# kinks_v41.net
KiCad netlist of a schematic drawn in EAGLE
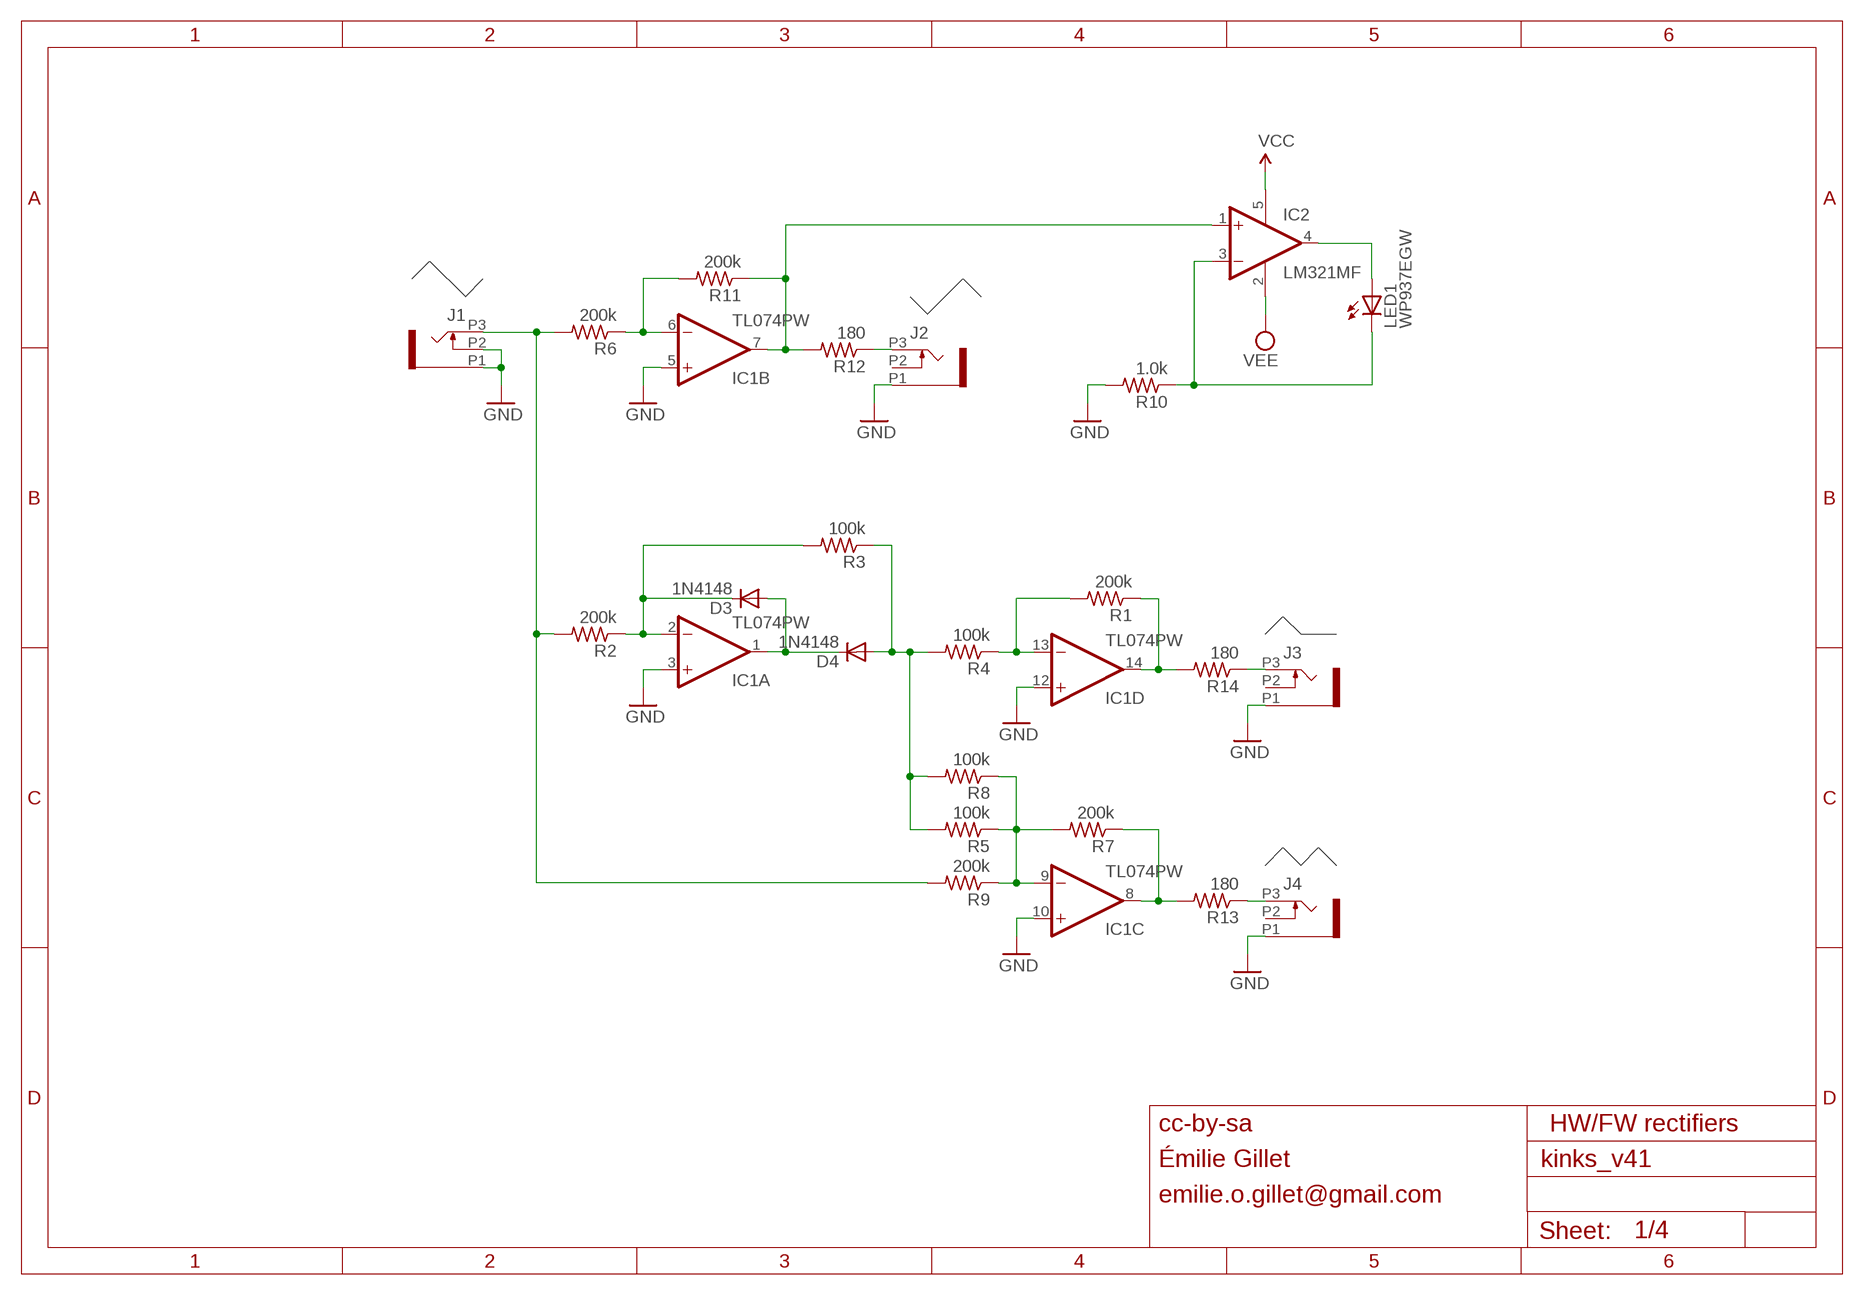
[diagram p0: schematic, sheet 1]
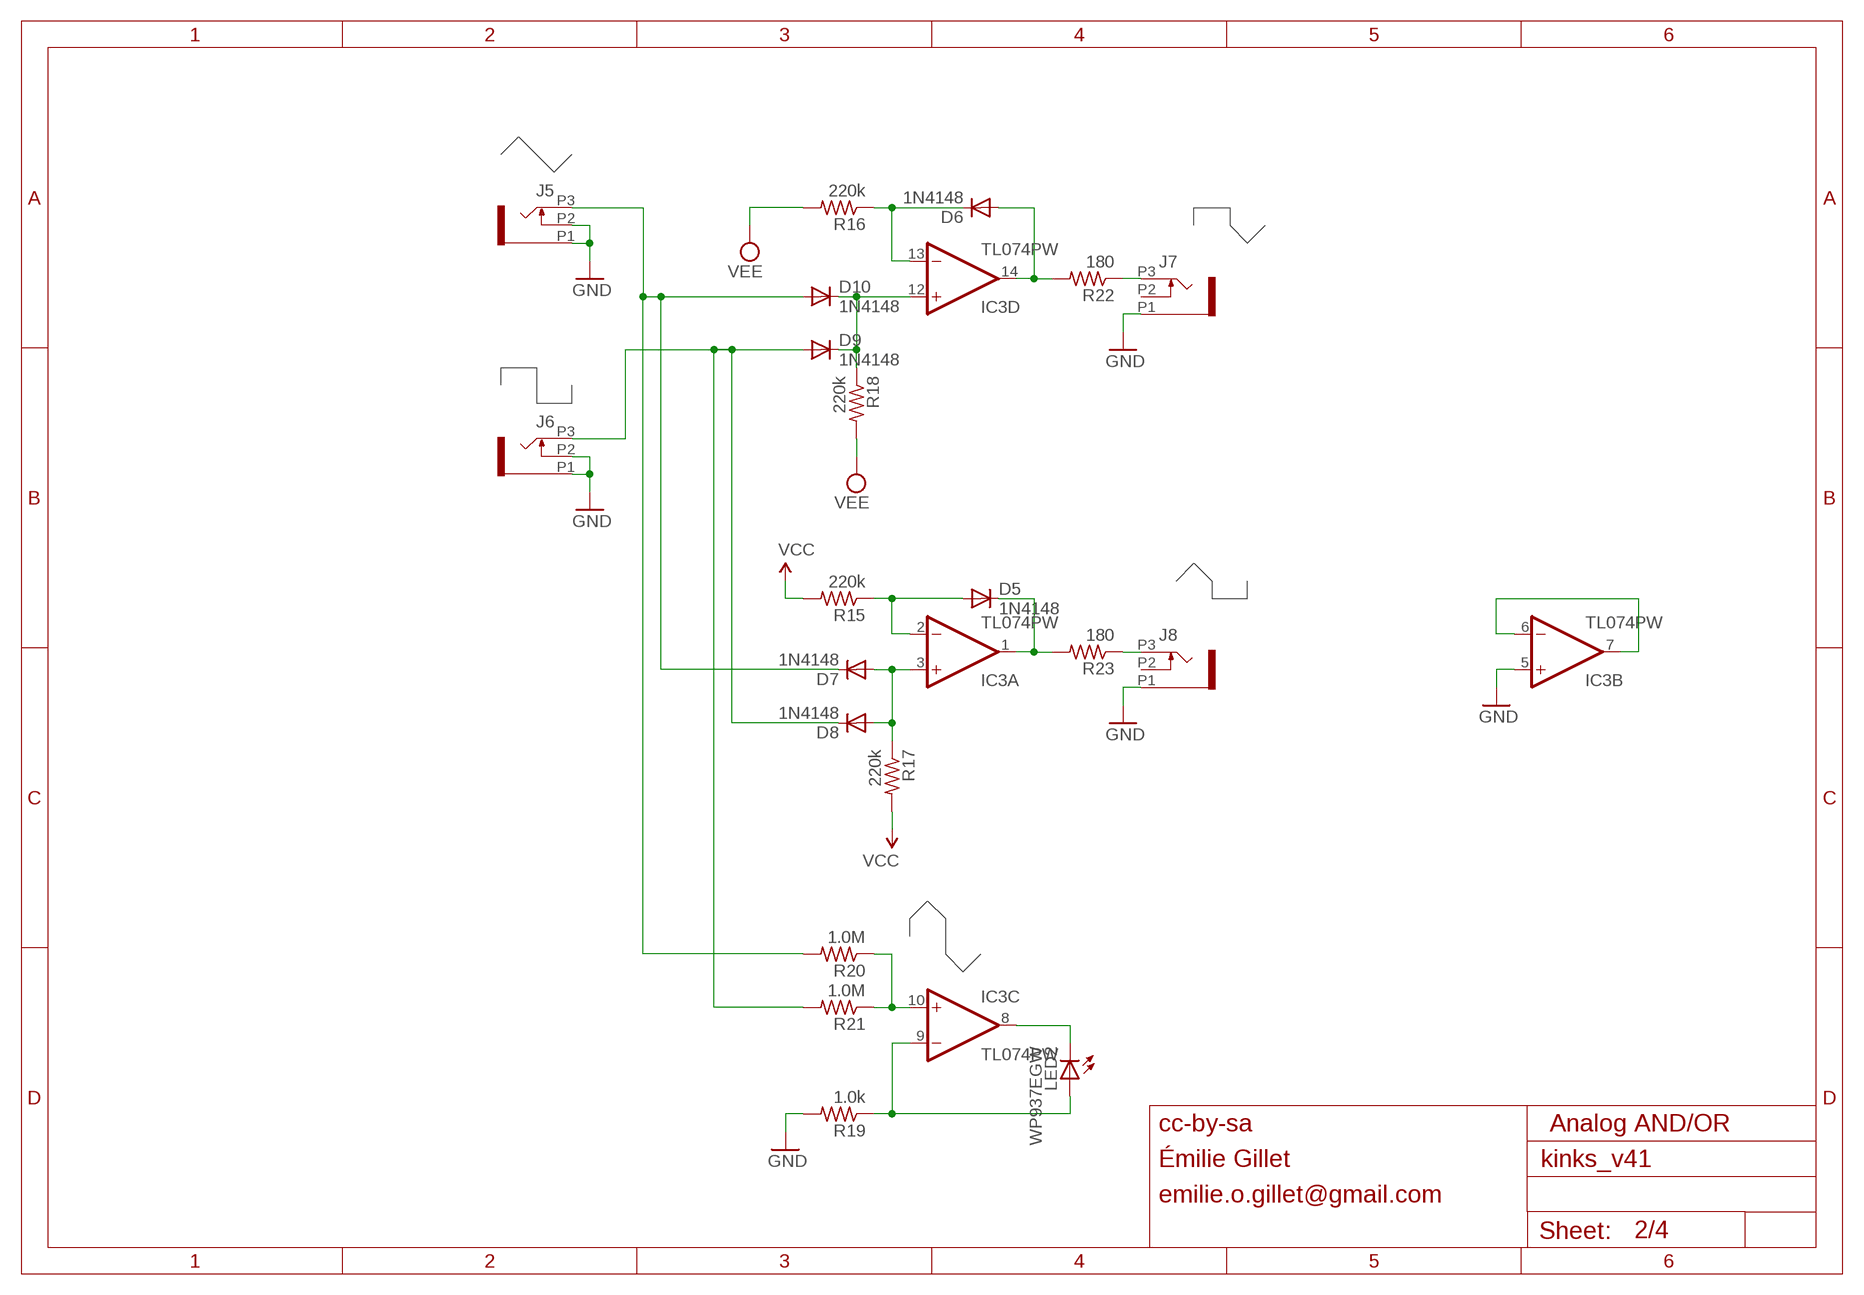
[diagram p1: schematic, sheet 2]
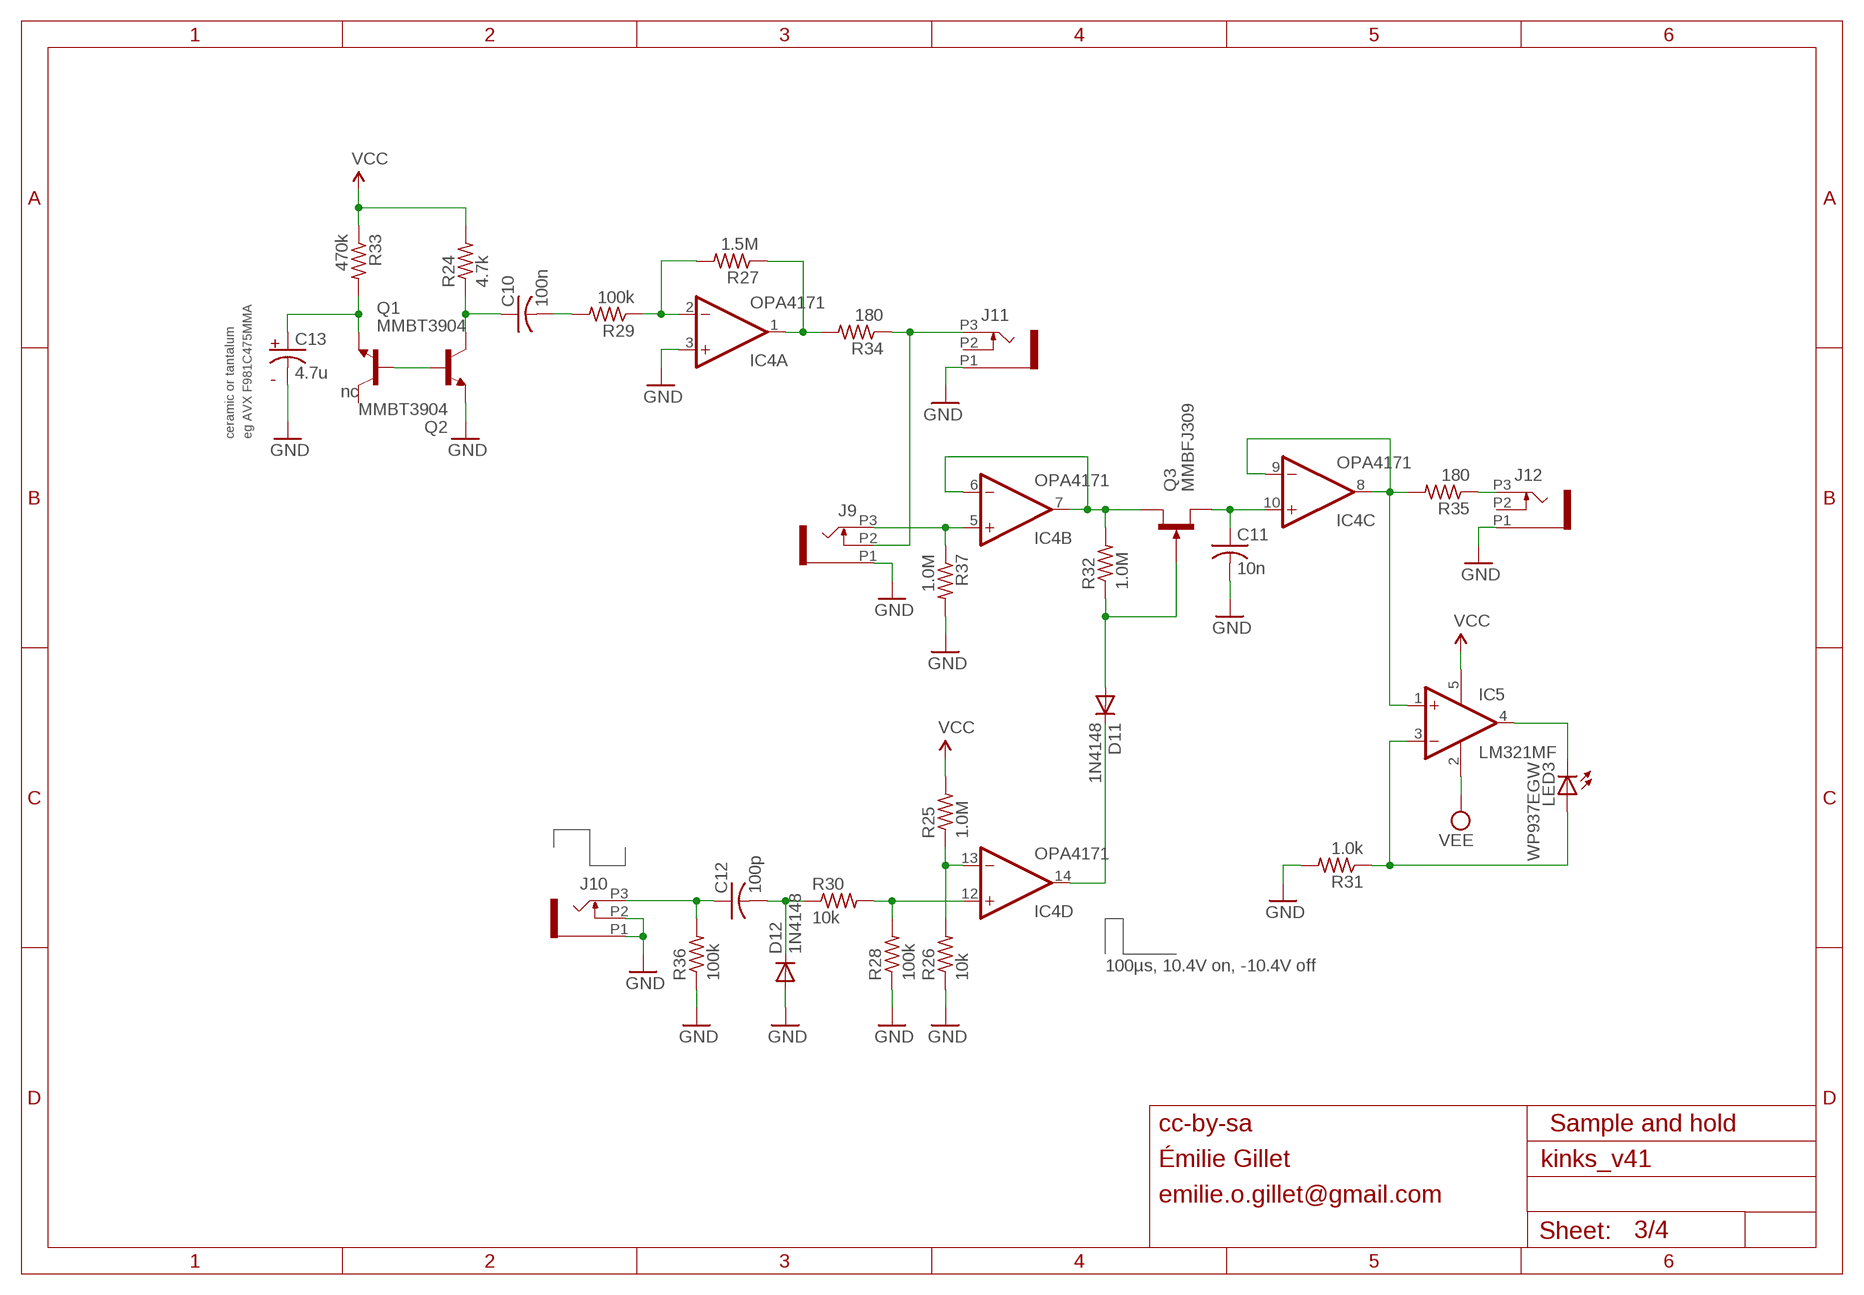
[diagram p2: schematic, sheet 3]
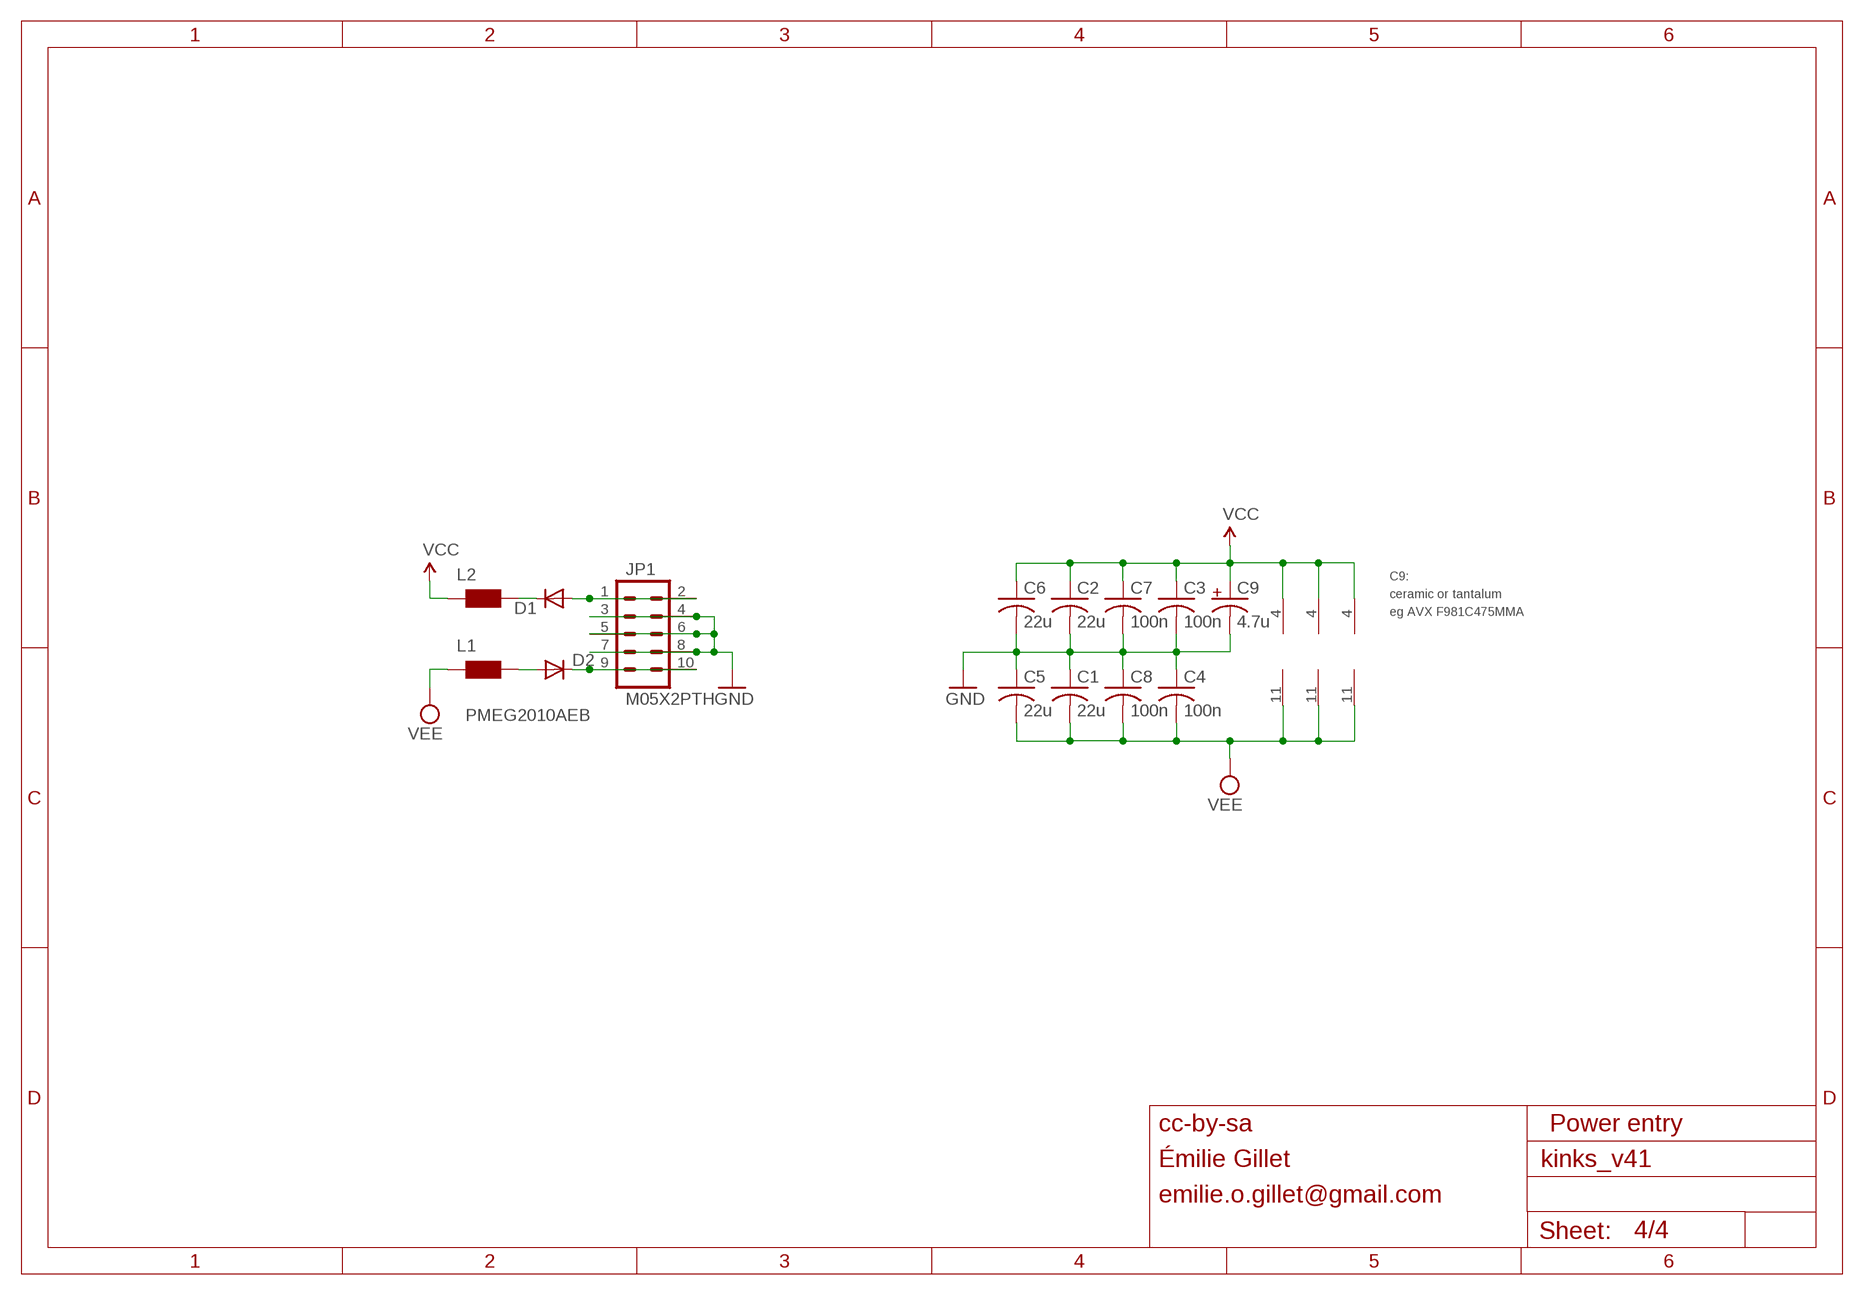
[diagram p3: schematic, sheet 4]

(export (version "E")
  (design (tool "Eeschema 10.0.6"))
  (components
    (comp (ref "C1")
      (value "22u")
      (footprint "eagle-import:C0805")
      (libsource (lib "eagle-import") (part "C-USC0805"))
    )
    (comp (ref "C2")
      (value "22u")
      (footprint "eagle-import:C0805")
      (libsource (lib "eagle-import") (part "C-USC0805"))
    )
    (comp (ref "C3")
      (value "100n")
      (footprint "eagle-import:C0402")
      (libsource (lib "eagle-import") (part "C-USC0402"))
    )
    (comp (ref "C4")
      (value "100n")
      (footprint "eagle-import:C0402")
      (libsource (lib "eagle-import") (part "C-USC0402"))
    )
    (comp (ref "C5")
      (value "22u")
      (footprint "eagle-import:C0805")
      (libsource (lib "eagle-import") (part "C-USC0805"))
    )
    (comp (ref "C6")
      (value "22u")
      (footprint "eagle-import:C0805")
      (libsource (lib "eagle-import") (part "C-USC0805"))
    )
    (comp (ref "C7")
      (value "100n")
      (footprint "eagle-import:C0402")
      (libsource (lib "eagle-import") (part "C-USC0402"))
    )
    (comp (ref "C8")
      (value "100n")
      (footprint "eagle-import:C0402")
      (libsource (lib "eagle-import") (part "C-USC0402"))
    )
    (comp (ref "C9")
      (value "4.7u")
      (footprint "eagle-import:C0603")
      (libsource (lib "eagle-import") (part "C-USC0603"))
    )
    (comp (ref "D1")
      (value "PMEG2010AEB")
      (footprint "eagle-import:SOD523")
      (libsource (lib "eagle-import") (part "DIODE-SOD523"))
    )
    (comp (ref "D2")
      (value "PMEG2010AEB")
      (footprint "eagle-import:SOD523")
      (libsource (lib "eagle-import") (part "DIODE-SOD523"))
    )
    (comp (ref "IC1")
      (value "TL074PW")
      (footprint "eagle-import:TSSOP14")
      (libsource (lib "eagle-import") (part "TL074PW"))
    )
    (comp (ref "IC3")
      (value "TL074PW")
      (footprint "eagle-import:TSSOP14")
      (libsource (lib "eagle-import") (part "TL074PW"))
    )
    (comp (ref "IC4")
      (value "OPA4171")
      (footprint "eagle-import:TSSOP14")
      (libsource (lib "eagle-import") (part "TL074PW"))
    )
    (comp (ref "JP1")
      (value "M05X2PTH")
      (footprint "eagle-import:AVR_ICSP")
      (libsource (lib "eagle-import") (part "M05X2PTH"))
    )
    (comp (ref "L1")
      (value "WE-CBF_0603")
      (footprint "eagle-import:0603")
      (libsource (lib "eagle-import") (part "WE-CBF_0603"))
    )
    (comp (ref "L2")
      (value "WE-CBF_0603")
      (footprint "eagle-import:0603")
      (libsource (lib "eagle-import") (part "WE-CBF_0603"))
    )
    (comp (ref "D3")
      (value "1N4148")
      (footprint "eagle-import:SOD523")
      (libsource (lib "eagle-import") (part "DIODE-SOD523"))
    )
    (comp (ref "D4")
      (value "1N4148")
      (footprint "eagle-import:SOD523")
      (libsource (lib "eagle-import") (part "DIODE-SOD523"))
    )
    (comp (ref "IC2")
      (value "LM321MF")
      (footprint "eagle-import:SOT23-5")
      (libsource (lib "eagle-import") (part "LM321?MF"))
    )
    (comp (ref "J1")
      (value "PJ301_THONKICONN6")
      (footprint "eagle-import:WQP_PJ_301M6")
      (libsource (lib "eagle-import") (part "PJ301_THONKICONN6"))
    )
    (comp (ref "J2")
      (value "PJ301_THONKICONN6")
      (footprint "eagle-import:WQP_PJ_301M6")
      (libsource (lib "eagle-import") (part "PJ301_THONKICONN6"))
    )
    (comp (ref "J3")
      (value "PJ301_THONKICONN6")
      (footprint "eagle-import:WQP_PJ_301M6")
      (libsource (lib "eagle-import") (part "PJ301_THONKICONN6"))
    )
    (comp (ref "J4")
      (value "PJ301_THONKICONN6")
      (footprint "eagle-import:WQP_PJ_301M6")
      (libsource (lib "eagle-import") (part "PJ301_THONKICONN6"))
    )
    (comp (ref "LED1")
      (value "WP937EGW")
      (footprint "eagle-import:LED3MM")
      (libsource (lib "eagle-import") (part "LED3MM"))
    )
    (comp (ref "R1")
      (value "200k")
      (footprint "eagle-import:R0402")
      (libsource (lib "eagle-import") (part "R-US_R0402"))
    )
    (comp (ref "R2")
      (value "200k")
      (footprint "eagle-import:R0402")
      (libsource (lib "eagle-import") (part "R-US_R0402"))
    )
    (comp (ref "R3")
      (value "100k")
      (footprint "eagle-import:R0402")
      (libsource (lib "eagle-import") (part "R-US_R0402"))
    )
    (comp (ref "R4")
      (value "100k")
      (footprint "eagle-import:R0402")
      (libsource (lib "eagle-import") (part "R-US_R0402"))
    )
    (comp (ref "R5")
      (value "100k")
      (footprint "eagle-import:R0402")
      (libsource (lib "eagle-import") (part "R-US_R0402"))
    )
    (comp (ref "R6")
      (value "200k")
      (footprint "eagle-import:R0402")
      (libsource (lib "eagle-import") (part "R-US_R0402"))
    )
    (comp (ref "R7")
      (value "200k")
      (footprint "eagle-import:R0402")
      (libsource (lib "eagle-import") (part "R-US_R0402"))
    )
    (comp (ref "R8")
      (value "100k")
      (footprint "eagle-import:R0402")
      (libsource (lib "eagle-import") (part "R-US_R0402"))
    )
    (comp (ref "R9")
      (value "200k")
      (footprint "eagle-import:R0402")
      (libsource (lib "eagle-import") (part "R-US_R0402"))
    )
    (comp (ref "R10")
      (value "1.0k")
      (footprint "eagle-import:R0402")
      (libsource (lib "eagle-import") (part "R-US_R0402"))
    )
    (comp (ref "R11")
      (value "200k")
      (footprint "eagle-import:R0402")
      (libsource (lib "eagle-import") (part "R-US_R0402"))
    )
    (comp (ref "R12")
      (value "180")
      (footprint "eagle-import:R0402")
      (libsource (lib "eagle-import") (part "R-US_R0402"))
    )
    (comp (ref "R13")
      (value "180")
      (footprint "eagle-import:R0402")
      (libsource (lib "eagle-import") (part "R-US_R0402"))
    )
    (comp (ref "R14")
      (value "180")
      (footprint "eagle-import:R0402")
      (libsource (lib "eagle-import") (part "R-US_R0402"))
    )
    (comp (ref "C10")
      (value "100n")
      (footprint "eagle-import:C0402")
      (libsource (lib "eagle-import") (part "C-USC0402"))
    )
    (comp (ref "C11")
      (value "10n")
      (footprint "eagle-import:C0603")
      (libsource (lib "eagle-import") (part "C-USC0603"))
    )
    (comp (ref "C12")
      (value "100p")
      (footprint "eagle-import:C0402")
      (libsource (lib "eagle-import") (part "C-USC0402"))
    )
    (comp (ref "C13")
      (value "4.7u")
      (footprint "eagle-import:C0603")
      (libsource (lib "eagle-import") (part "C-USC0603"))
    )
    (comp (ref "D11")
      (value "1N4148")
      (footprint "eagle-import:SOD523")
      (libsource (lib "eagle-import") (part "DIODE-SOD523"))
    )
    (comp (ref "D12")
      (value "1N4148")
      (footprint "eagle-import:SOD523")
      (libsource (lib "eagle-import") (part "DIODE-SOD523"))
    )
    (comp (ref "IC5")
      (value "LM321MF")
      (footprint "eagle-import:SOT23-5")
      (libsource (lib "eagle-import") (part "LM321?MF"))
    )
    (comp (ref "J9")
      (value "PJ301_THONKICONN6")
      (footprint "eagle-import:WQP_PJ_301M6")
      (libsource (lib "eagle-import") (part "PJ301_THONKICONN6"))
    )
    (comp (ref "J10")
      (value "PJ301_THONKICONN6")
      (footprint "eagle-import:WQP_PJ_301M6")
      (libsource (lib "eagle-import") (part "PJ301_THONKICONN6"))
    )
    (comp (ref "J11")
      (value "PJ301_THONKICONN6")
      (footprint "eagle-import:WQP_PJ_301M6")
      (libsource (lib "eagle-import") (part "PJ301_THONKICONN6"))
    )
    (comp (ref "J12")
      (value "PJ301_THONKICONN6")
      (footprint "eagle-import:WQP_PJ_301M6")
      (libsource (lib "eagle-import") (part "PJ301_THONKICONN6"))
    )
    (comp (ref "LED3")
      (value "WP937EGW")
      (footprint "eagle-import:LED3MM")
      (libsource (lib "eagle-import") (part "LED3MM"))
    )
    (comp (ref "Q1")
      (value "MMBT3904")
      (footprint "eagle-import:SOT23-BEC")
      (libsource (lib "eagle-import") (part "-NPN-SOT23-BECMMBT3904LT1"))
    )
    (comp (ref "Q2")
      (value "MMBT3904")
      (footprint "eagle-import:SOT23-BEC")
      (libsource (lib "eagle-import") (part "-NPN-SOT23-BECMMBT3904LT1"))
    )
    (comp (ref "Q3")
      (value "MMBFJ309")
      (footprint "eagle-import:SOT23")
      (libsource (lib "eagle-import") (part "MMBFJ3"))
    )
    (comp (ref "R24")
      (value "4.7k")
      (footprint "eagle-import:R0402")
      (libsource (lib "eagle-import") (part "R-US_R0402"))
    )
    (comp (ref "R25")
      (value "1.0M")
      (footprint "eagle-import:R0402")
      (libsource (lib "eagle-import") (part "R-US_R0402"))
    )
    (comp (ref "R26")
      (value "10k")
      (footprint "eagle-import:R0402")
      (libsource (lib "eagle-import") (part "R-US_R0402"))
    )
    (comp (ref "R27")
      (value "1.5M")
      (footprint "eagle-import:R0402")
      (libsource (lib "eagle-import") (part "R-US_R0402"))
    )
    (comp (ref "R28")
      (value "100k")
      (footprint "eagle-import:R0402")
      (libsource (lib "eagle-import") (part "R-US_R0402"))
    )
    (comp (ref "R29")
      (value "100k")
      (footprint "eagle-import:R0402")
      (libsource (lib "eagle-import") (part "R-US_R0402"))
    )
    (comp (ref "R30")
      (value "10k")
      (footprint "eagle-import:R0402")
      (libsource (lib "eagle-import") (part "R-US_R0402"))
    )
    (comp (ref "R31")
      (value "1.0k")
      (footprint "eagle-import:R0402")
      (libsource (lib "eagle-import") (part "R-US_R0402"))
    )
    (comp (ref "R32")
      (value "1.0M")
      (footprint "eagle-import:R0402")
      (libsource (lib "eagle-import") (part "R-US_R0402"))
    )
    (comp (ref "R33")
      (value "470k")
      (footprint "eagle-import:R0402")
      (libsource (lib "eagle-import") (part "R-US_R0402"))
    )
    (comp (ref "R34")
      (value "180")
      (footprint "eagle-import:R0402")
      (libsource (lib "eagle-import") (part "R-US_R0402"))
    )
    (comp (ref "R35")
      (value "180")
      (footprint "eagle-import:R0402")
      (libsource (lib "eagle-import") (part "R-US_R0402"))
    )
    (comp (ref "R36")
      (value "100k")
      (footprint "eagle-import:R0402")
      (libsource (lib "eagle-import") (part "R-US_R0402"))
    )
    (comp (ref "R37")
      (value "1.0M")
      (footprint "eagle-import:R0402")
      (libsource (lib "eagle-import") (part "R-US_R0402"))
    )
    (comp (ref "D5")
      (value "1N4148")
      (footprint "eagle-import:SOD523")
      (libsource (lib "eagle-import") (part "DIODE-SOD523"))
    )
    (comp (ref "D6")
      (value "1N4148")
      (footprint "eagle-import:SOD523")
      (libsource (lib "eagle-import") (part "DIODE-SOD523"))
    )
    (comp (ref "D7")
      (value "1N4148")
      (footprint "eagle-import:SOD523")
      (libsource (lib "eagle-import") (part "DIODE-SOD523"))
    )
    (comp (ref "D8")
      (value "1N4148")
      (footprint "eagle-import:SOD523")
      (libsource (lib "eagle-import") (part "DIODE-SOD523"))
    )
    (comp (ref "D9")
      (value "1N4148")
      (footprint "eagle-import:SOD523")
      (libsource (lib "eagle-import") (part "DIODE-SOD523"))
    )
    (comp (ref "D10")
      (value "1N4148")
      (footprint "eagle-import:SOD523")
      (libsource (lib "eagle-import") (part "DIODE-SOD523"))
    )
    (comp (ref "J5")
      (value "PJ301_THONKICONN6")
      (footprint "eagle-import:WQP_PJ_301M6")
      (libsource (lib "eagle-import") (part "PJ301_THONKICONN6"))
    )
    (comp (ref "J6")
      (value "PJ301_THONKICONN6")
      (footprint "eagle-import:WQP_PJ_301M6")
      (libsource (lib "eagle-import") (part "PJ301_THONKICONN6"))
    )
    (comp (ref "J7")
      (value "PJ301_THONKICONN6")
      (footprint "eagle-import:WQP_PJ_301M6")
      (libsource (lib "eagle-import") (part "PJ301_THONKICONN6"))
    )
    (comp (ref "J8")
      (value "PJ301_THONKICONN6")
      (footprint "eagle-import:WQP_PJ_301M6")
      (libsource (lib "eagle-import") (part "PJ301_THONKICONN6"))
    )
    (comp (ref "LED2")
      (value "WP937EGW")
      (footprint "eagle-import:LED3MM")
      (libsource (lib "eagle-import") (part "LED3MM"))
    )
    (comp (ref "R15")
      (value "220k")
      (footprint "eagle-import:R0402")
      (libsource (lib "eagle-import") (part "R-US_R0402"))
    )
    (comp (ref "R16")
      (value "220k")
      (footprint "eagle-import:R0402")
      (libsource (lib "eagle-import") (part "R-US_R0402"))
    )
    (comp (ref "R17")
      (value "220k")
      (footprint "eagle-import:R0402")
      (libsource (lib "eagle-import") (part "R-US_R0402"))
    )
    (comp (ref "R18")
      (value "220k")
      (footprint "eagle-import:R0402")
      (libsource (lib "eagle-import") (part "R-US_R0402"))
    )
    (comp (ref "R19")
      (value "1.0k")
      (footprint "eagle-import:R0402")
      (libsource (lib "eagle-import") (part "R-US_R0402"))
    )
    (comp (ref "R20")
      (value "1.0M")
      (footprint "eagle-import:R0402")
      (libsource (lib "eagle-import") (part "R-US_R0402"))
    )
    (comp (ref "R21")
      (value "1.0M")
      (footprint "eagle-import:R0402")
      (libsource (lib "eagle-import") (part "R-US_R0402"))
    )
    (comp (ref "R22")
      (value "180")
      (footprint "eagle-import:R0402")
      (libsource (lib "eagle-import") (part "R-US_R0402"))
    )
    (comp (ref "R23")
      (value "180")
      (footprint "eagle-import:R0402")
      (libsource (lib "eagle-import") (part "R-US_R0402"))
    )
  )
  (nets
    (net (code "1") (name "GND") (class "Default")
      (node (ref "C1") (pin "1") (pinfunction "1_1") (pintype "passive"))
      (node (ref "C11") (pin "2") (pinfunction "2_2") (pintype "passive"))
      (node (ref "C13") (pin "2") (pinfunction "2_2") (pintype "passive"))
      (node (ref "C2") (pin "2") (pinfunction "2_2") (pintype "passive"))
      (node (ref "C3") (pin "2") (pinfunction "2_2") (pintype "passive"))
      (node (ref "C4") (pin "1") (pinfunction "1_1") (pintype "passive"))
      (node (ref "C5") (pin "1") (pinfunction "1_1") (pintype "passive"))
      (node (ref "C6") (pin "2") (pinfunction "2_2") (pintype "passive"))
      (node (ref "C7") (pin "2") (pinfunction "2_2") (pintype "passive"))
      (node (ref "C8") (pin "1") (pinfunction "1_1") (pintype "passive"))
      (node (ref "C9") (pin "2") (pinfunction "2_2") (pintype "passive"))
      (node (ref "D12") (pin "A") (pinfunction "A_A") (pintype "passive"))
      (node (ref "IC1") (pin "10") (pinfunction "+IN_10") (pintype "input"))
      (node (ref "IC1") (pin "12") (pinfunction "+IN_12") (pintype "input"))
      (node (ref "IC1") (pin "3") (pinfunction "+IN_3") (pintype "input"))
      (node (ref "IC1") (pin "5") (pinfunction "+IN_5") (pintype "input"))
      (node (ref "IC3") (pin "5") (pinfunction "+IN_5") (pintype "input"))
      (node (ref "IC4") (pin "3") (pinfunction "+IN_3") (pintype "input"))
      (node (ref "J1") (pin "P1") (pinfunction "1_P1") (pintype "passive"))
      (node (ref "J1") (pin "P2") (pinfunction "2_P2") (pintype "passive"))
      (node (ref "J10") (pin "P1") (pinfunction "1_P1") (pintype "passive"))
      (node (ref "J10") (pin "P2") (pinfunction "2_P2") (pintype "passive"))
      (node (ref "J11") (pin "P1") (pinfunction "1_P1") (pintype "passive"))
      (node (ref "J12") (pin "P1") (pinfunction "1_P1") (pintype "passive"))
      (node (ref "J2") (pin "P1") (pinfunction "1_P1") (pintype "passive"))
      (node (ref "J3") (pin "P1") (pinfunction "1_P1") (pintype "passive"))
      (node (ref "J4") (pin "P1") (pinfunction "1_P1") (pintype "passive"))
      (node (ref "J5") (pin "P1") (pinfunction "1_P1") (pintype "passive"))
      (node (ref "J5") (pin "P2") (pinfunction "2_P2") (pintype "passive"))
      (node (ref "J6") (pin "P1") (pinfunction "1_P1") (pintype "passive"))
      (node (ref "J6") (pin "P2") (pinfunction "2_P2") (pintype "passive"))
      (node (ref "J7") (pin "P1") (pinfunction "1_P1") (pintype "passive"))
      (node (ref "J8") (pin "P1") (pinfunction "1_P1") (pintype "passive"))
      (node (ref "J9") (pin "P1") (pinfunction "1_P1") (pintype "passive"))
      (node (ref "JP1") (pin "3") (pinfunction "3_3") (pintype "passive"))
      (node (ref "JP1") (pin "4") (pinfunction "4_4") (pintype "passive"))
      (node (ref "JP1") (pin "5") (pinfunction "5_5") (pintype "passive"))
      (node (ref "JP1") (pin "6") (pinfunction "6_6") (pintype "passive"))
      (node (ref "JP1") (pin "7") (pinfunction "7_7") (pintype "passive"))
      (node (ref "JP1") (pin "8") (pinfunction "8_8") (pintype "passive"))
      (node (ref "Q1") (pin "E") (pinfunction "E_E") (pintype "passive"))
      (node (ref "R10") (pin "2") (pinfunction "2_2") (pintype "passive"))
      (node (ref "R19") (pin "2") (pinfunction "2_2") (pintype "passive"))
      (node (ref "R26") (pin "1") (pinfunction "1_1") (pintype "passive"))
      (node (ref "R28") (pin "1") (pinfunction "1_1") (pintype "passive"))
      (node (ref "R31") (pin "2") (pinfunction "2_2") (pintype "passive"))
      (node (ref "R36") (pin "1") (pinfunction "1_1") (pintype "passive"))
      (node (ref "R37") (pin "2") (pinfunction "2_2") (pintype "passive"))
    )
    (net (code "2") (name "Net-(C10-Pad1)") (class "Default")
      (node (ref "C10") (pin "1") (pinfunction "1_1") (pintype "passive"))
      (node (ref "Q1") (pin "C") (pinfunction "C_C") (pintype "passive"))
      (node (ref "R24") (pin "1") (pinfunction "1_1") (pintype "passive"))
    )
    (net (code "3") (name "Net-(C10-Pad2)") (class "Default")
      (node (ref "C10") (pin "2") (pinfunction "2_2") (pintype "passive"))
      (node (ref "R29") (pin "2") (pinfunction "2_2") (pintype "passive"))
    )
    (net (code "4") (name "Net-(C12-Pad2)") (class "Default")
      (node (ref "C12") (pin "2") (pinfunction "2_2") (pintype "passive"))
      (node (ref "D12") (pin "C") (pinfunction "C_C") (pintype "passive"))
      (node (ref "R30") (pin "1") (pinfunction "1_1") (pintype "passive"))
    )
    (net (code "5") (name "Net-(C13-Pad1)") (class "Default")
      (node (ref "C13") (pin "1") (pinfunction "1_1") (pintype "passive"))
      (node (ref "Q2") (pin "E") (pinfunction "E_E") (pintype "passive"))
      (node (ref "R33") (pin "2") (pinfunction "2_2") (pintype "passive"))
    )
    (net (code "6") (name "Net-(D1-PadA)") (class "Default")
      (node (ref "D1") (pin "A") (pinfunction "A_A") (pintype "passive"))
      (node (ref "JP1") (pin "1") (pinfunction "1_1") (pintype "passive"))
      (node (ref "JP1") (pin "2") (pinfunction "2_2") (pintype "passive"))
    )
    (net (code "7") (name "Net-(D1-PadC)") (class "Default")
      (node (ref "D1") (pin "C") (pinfunction "C_C") (pintype "passive"))
      (node (ref "L2") (pin "2") (pinfunction "2_2") (pintype "passive"))
    )
    (net (code "8") (name "Net-(D2-PadA)") (class "Default")
      (node (ref "D2") (pin "A") (pinfunction "A_A") (pintype "passive"))
      (node (ref "L1") (pin "2") (pinfunction "2_2") (pintype "passive"))
    )
    (net (code "9") (name "Net-(D2-PadC)") (class "Default")
      (node (ref "D2") (pin "C") (pinfunction "C_C") (pintype "passive"))
      (node (ref "JP1") (pin "10") (pinfunction "10_10") (pintype "passive"))
      (node (ref "JP1") (pin "9") (pinfunction "9_9") (pintype "passive"))
    )
    (net (code "10") (name "Net-(D4-PadA)") (class "Default")
      (node (ref "D4") (pin "A") (pinfunction "A_A") (pintype "passive"))
      (node (ref "R3") (pin "1") (pinfunction "1_1") (pintype "passive"))
      (node (ref "R4") (pin "2") (pinfunction "2_2") (pintype "passive"))
      (node (ref "R5") (pin "2") (pinfunction "2_2") (pintype "passive"))
      (node (ref "R8") (pin "2") (pinfunction "2_2") (pintype "passive"))
    )
    (net (code "11") (name "Net-(IC1A--IN)") (class "Default")
      (node (ref "D3") (pin "C") (pinfunction "C_C") (pintype "passive"))
      (node (ref "IC1") (pin "2") (pinfunction "-IN_2") (pintype "input"))
      (node (ref "R2") (pin "1") (pinfunction "1_1") (pintype "passive"))
      (node (ref "R3") (pin "2") (pinfunction "2_2") (pintype "passive"))
    )
    (net (code "12") (name "Net-(IC1A-OUT)") (class "Default")
      (node (ref "D3") (pin "A") (pinfunction "A_A") (pintype "passive"))
      (node (ref "D4") (pin "C") (pinfunction "C_C") (pintype "passive"))
      (node (ref "IC1") (pin "1") (pinfunction "OUT_1") (pintype "output"))
    )
    (net (code "13") (name "Net-(IC1B--IN)") (class "Default")
      (node (ref "IC1") (pin "6") (pinfunction "-IN_6") (pintype "input"))
      (node (ref "R11") (pin "2") (pinfunction "2_2") (pintype "passive"))
      (node (ref "R6") (pin "1") (pinfunction "1_1") (pintype "passive"))
    )
    (net (code "14") (name "Net-(IC1B-OUT)") (class "Default")
      (node (ref "IC1") (pin "7") (pinfunction "OUT_7") (pintype "output"))
      (node (ref "IC2") (pin "1") (pinfunction "+IN_1") (pintype "input"))
      (node (ref "R11") (pin "1") (pinfunction "1_1") (pintype "passive"))
      (node (ref "R12") (pin "2") (pinfunction "2_2") (pintype "passive"))
    )
    (net (code "15") (name "Net-(IC1C--IN)") (class "Default")
      (node (ref "IC1") (pin "9") (pinfunction "-IN_9") (pintype "input"))
      (node (ref "R5") (pin "1") (pinfunction "1_1") (pintype "passive"))
      (node (ref "R7") (pin "2") (pinfunction "2_2") (pintype "passive"))
      (node (ref "R8") (pin "1") (pinfunction "1_1") (pintype "passive"))
      (node (ref "R9") (pin "1") (pinfunction "1_1") (pintype "passive"))
    )
    (net (code "16") (name "Net-(IC1C-OUT)") (class "Default")
      (node (ref "IC1") (pin "8") (pinfunction "OUT_8") (pintype "output"))
      (node (ref "R13") (pin "2") (pinfunction "2_2") (pintype "passive"))
      (node (ref "R7") (pin "1") (pinfunction "1_1") (pintype "passive"))
    )
    (net (code "17") (name "Net-(IC1D--IN)") (class "Default")
      (node (ref "IC1") (pin "13") (pinfunction "-IN_13") (pintype "input"))
      (node (ref "R1") (pin "2") (pinfunction "2_2") (pintype "passive"))
      (node (ref "R4") (pin "1") (pinfunction "1_1") (pintype "passive"))
    )
    (net (code "18") (name "Net-(IC1D-OUT)") (class "Default")
      (node (ref "IC1") (pin "14") (pinfunction "OUT_14") (pintype "output"))
      (node (ref "R1") (pin "1") (pinfunction "1_1") (pintype "passive"))
      (node (ref "R14") (pin "2") (pinfunction "2_2") (pintype "passive"))
    )
    (net (code "19") (name "Net-(IC2--IN)") (class "Default")
      (node (ref "IC2") (pin "3") (pinfunction "-IN_3") (pintype "input"))
      (node (ref "LED1") (pin "K") (pinfunction "C_K") (pintype "passive"))
      (node (ref "R10") (pin "1") (pinfunction "1_1") (pintype "passive"))
    )
    (net (code "20") (name "Net-(IC2-OUT)") (class "Default")
      (node (ref "IC2") (pin "4") (pinfunction "OUT_4") (pintype "output"))
      (node (ref "LED1") (pin "A") (pinfunction "A_A") (pintype "passive"))
    )
    (net (code "21") (name "Net-(IC3A-+IN)") (class "Default")
      (node (ref "D7") (pin "A") (pinfunction "A_A") (pintype "passive"))
      (node (ref "D8") (pin "A") (pinfunction "A_A") (pintype "passive"))
      (node (ref "IC3") (pin "3") (pinfunction "+IN_3") (pintype "input"))
      (node (ref "R17") (pin "1") (pinfunction "1_1") (pintype "passive"))
    )
    (net (code "22") (name "Net-(IC3A--IN)") (class "Default")
      (node (ref "D5") (pin "A") (pinfunction "A_A") (pintype "passive"))
      (node (ref "IC3") (pin "2") (pinfunction "-IN_2") (pintype "input"))
      (node (ref "R15") (pin "1") (pinfunction "1_1") (pintype "passive"))
    )
    (net (code "23") (name "Net-(IC3A-OUT)") (class "Default")
      (node (ref "D5") (pin "C") (pinfunction "C_C") (pintype "passive"))
      (node (ref "IC3") (pin "1") (pinfunction "OUT_1") (pintype "output"))
      (node (ref "R23") (pin "2") (pinfunction "2_2") (pintype "passive"))
    )
    (net (code "24") (name "Net-(IC3B--IN)") (class "Default")
      (node (ref "IC3") (pin "6") (pinfunction "-IN_6") (pintype "input"))
      (node (ref "IC3") (pin "7") (pinfunction "OUT_7") (pintype "output"))
    )
    (net (code "25") (name "Net-(IC3C-+IN)") (class "Default")
      (node (ref "IC3") (pin "10") (pinfunction "+IN_10") (pintype "input"))
      (node (ref "R20") (pin "1") (pinfunction "1_1") (pintype "passive"))
      (node (ref "R21") (pin "1") (pinfunction "1_1") (pintype "passive"))
    )
    (net (code "26") (name "Net-(IC3C--IN)") (class "Default")
      (node (ref "IC3") (pin "9") (pinfunction "-IN_9") (pintype "input"))
      (node (ref "LED2") (pin "A") (pinfunction "A_A") (pintype "passive"))
      (node (ref "R19") (pin "1") (pinfunction "1_1") (pintype "passive"))
    )
    (net (code "27") (name "Net-(IC3C-OUT)") (class "Default")
      (node (ref "IC3") (pin "8") (pinfunction "OUT_8") (pintype "output"))
      (node (ref "LED2") (pin "K") (pinfunction "C_K") (pintype "passive"))
    )
    (net (code "28") (name "Net-(IC3D-+IN)") (class "Default")
      (node (ref "D10") (pin "C") (pinfunction "C_C") (pintype "passive"))
      (node (ref "D9") (pin "C") (pinfunction "C_C") (pintype "passive"))
      (node (ref "IC3") (pin "12") (pinfunction "+IN_12") (pintype "input"))
      (node (ref "R18") (pin "1") (pinfunction "1_1") (pintype "passive"))
    )
    (net (code "29") (name "Net-(IC3D--IN)") (class "Default")
      (node (ref "D6") (pin "C") (pinfunction "C_C") (pintype "passive"))
      (node (ref "IC3") (pin "13") (pinfunction "-IN_13") (pintype "input"))
      (node (ref "R16") (pin "1") (pinfunction "1_1") (pintype "passive"))
    )
    (net (code "30") (name "Net-(IC3D-OUT)") (class "Default")
      (node (ref "D6") (pin "A") (pinfunction "A_A") (pintype "passive"))
      (node (ref "IC3") (pin "14") (pinfunction "OUT_14") (pintype "output"))
      (node (ref "R22") (pin "2") (pinfunction "2_2") (pintype "passive"))
    )
    (net (code "31") (name "Net-(IC4A--IN)") (class "Default")
      (node (ref "IC4") (pin "2") (pinfunction "-IN_2") (pintype "input"))
      (node (ref "R27") (pin "2") (pinfunction "2_2") (pintype "passive"))
      (node (ref "R29") (pin "1") (pinfunction "1_1") (pintype "passive"))
    )
    (net (code "32") (name "Net-(IC4A-OUT)") (class "Default")
      (node (ref "IC4") (pin "1") (pinfunction "OUT_1") (pintype "output"))
      (node (ref "R27") (pin "1") (pinfunction "1_1") (pintype "passive"))
      (node (ref "R34") (pin "2") (pinfunction "2_2") (pintype "passive"))
    )
    (net (code "33") (name "Net-(IC4B-+IN)") (class "Default")
      (node (ref "IC4") (pin "5") (pinfunction "+IN_5") (pintype "input"))
      (node (ref "J9") (pin "P3") (pinfunction "3_P3") (pintype "passive"))
      (node (ref "R37") (pin "1") (pinfunction "1_1") (pintype "passive"))
    )
    (net (code "34") (name "Net-(IC4B--IN)") (class "Default")
      (node (ref "IC4") (pin "6") (pinfunction "-IN_6") (pintype "input"))
      (node (ref "IC4") (pin "7") (pinfunction "OUT_7") (pintype "output"))
      (node (ref "Q3") (pin "1") (pinfunction "D_1") (pintype "passive"))
      (node (ref "R32") (pin "2") (pinfunction "2_2") (pintype "passive"))
    )
    (net (code "35") (name "Net-(IC4C-+IN)") (class "Default")
      (node (ref "C11") (pin "1") (pinfunction "1_1") (pintype "passive"))
      (node (ref "IC4") (pin "10") (pinfunction "+IN_10") (pintype "input"))
      (node (ref "Q3") (pin "2") (pinfunction "S_2") (pintype "passive"))
    )
    (net (code "36") (name "Net-(IC4C--IN)") (class "Default")
      (node (ref "IC4") (pin "8") (pinfunction "OUT_8") (pintype "output"))
      (node (ref "IC4") (pin "9") (pinfunction "-IN_9") (pintype "input"))
      (node (ref "IC5") (pin "1") (pinfunction "+IN_1") (pintype "input"))
      (node (ref "R35") (pin "2") (pinfunction "2_2") (pintype "passive"))
    )
    (net (code "37") (name "Net-(IC4D-+IN)") (class "Default")
      (node (ref "IC4") (pin "12") (pinfunction "+IN_12") (pintype "input"))
      (node (ref "R28") (pin "2") (pinfunction "2_2") (pintype "passive"))
      (node (ref "R30") (pin "2") (pinfunction "2_2") (pintype "passive"))
    )
    (net (code "38") (name "Net-(IC4D--IN)") (class "Default")
      (node (ref "IC4") (pin "13") (pinfunction "-IN_13") (pintype "input"))
      (node (ref "R25") (pin "1") (pinfunction "1_1") (pintype "passive"))
      (node (ref "R26") (pin "2") (pinfunction "2_2") (pintype "passive"))
    )
    (net (code "39") (name "Net-(IC4D-OUT)") (class "Default")
      (node (ref "D11") (pin "C") (pinfunction "C_C") (pintype "passive"))
      (node (ref "IC4") (pin "14") (pinfunction "OUT_14") (pintype "output"))
    )
    (net (code "40") (name "Net-(IC5--IN)") (class "Default")
      (node (ref "IC5") (pin "3") (pinfunction "-IN_3") (pintype "input"))
      (node (ref "LED3") (pin "A") (pinfunction "A_A") (pintype "passive"))
      (node (ref "R31") (pin "1") (pinfunction "1_1") (pintype "passive"))
    )
    (net (code "41") (name "Net-(IC5-OUT)") (class "Default")
      (node (ref "IC5") (pin "4") (pinfunction "OUT_4") (pintype "output"))
      (node (ref "LED3") (pin "K") (pinfunction "C_K") (pintype "passive"))
    )
    (net (code "42") (name "Net-(J1-3)") (class "Default")
      (node (ref "J1") (pin "P3") (pinfunction "3_P3") (pintype "passive"))
      (node (ref "R2") (pin "2") (pinfunction "2_2") (pintype "passive"))
      (node (ref "R6") (pin "2") (pinfunction "2_2") (pintype "passive"))
      (node (ref "R9") (pin "2") (pinfunction "2_2") (pintype "passive"))
    )
    (net (code "43") (name "Net-(J2-3)") (class "Default")
      (node (ref "J2") (pin "P3") (pinfunction "3_P3") (pintype "passive"))
      (node (ref "R12") (pin "1") (pinfunction "1_1") (pintype "passive"))
    )
    (net (code "44") (name "Net-(J3-3)") (class "Default")
      (node (ref "J3") (pin "P3") (pinfunction "3_P3") (pintype "passive"))
      (node (ref "R14") (pin "1") (pinfunction "1_1") (pintype "passive"))
    )
    (net (code "45") (name "Net-(J4-3)") (class "Default")
      (node (ref "J4") (pin "P3") (pinfunction "3_P3") (pintype "passive"))
      (node (ref "R13") (pin "1") (pinfunction "1_1") (pintype "passive"))
    )
    (net (code "46") (name "Net-(J5-3)") (class "Default")
      (node (ref "D10") (pin "A") (pinfunction "A_A") (pintype "passive"))
      (node (ref "D7") (pin "C") (pinfunction "C_C") (pintype "passive"))
      (node (ref "J5") (pin "P3") (pinfunction "3_P3") (pintype "passive"))
      (node (ref "R20") (pin "2") (pinfunction "2_2") (pintype "passive"))
    )
    (net (code "47") (name "Net-(J6-3)") (class "Default")
      (node (ref "D8") (pin "C") (pinfunction "C_C") (pintype "passive"))
      (node (ref "D9") (pin "A") (pinfunction "A_A") (pintype "passive"))
      (node (ref "J6") (pin "P3") (pinfunction "3_P3") (pintype "passive"))
      (node (ref "R21") (pin "2") (pinfunction "2_2") (pintype "passive"))
    )
    (net (code "48") (name "Net-(J7-3)") (class "Default")
      (node (ref "J7") (pin "P3") (pinfunction "3_P3") (pintype "passive"))
      (node (ref "R22") (pin "1") (pinfunction "1_1") (pintype "passive"))
    )
    (net (code "49") (name "Net-(J8-3)") (class "Default")
      (node (ref "J8") (pin "P3") (pinfunction "3_P3") (pintype "passive"))
      (node (ref "R23") (pin "1") (pinfunction "1_1") (pintype "passive"))
    )
    (net (code "50") (name "Net-(J10-3)") (class "Default")
      (node (ref "C12") (pin "1") (pinfunction "1_1") (pintype "passive"))
      (node (ref "J10") (pin "P3") (pinfunction "3_P3") (pintype "passive"))
      (node (ref "R36") (pin "2") (pinfunction "2_2") (pintype "passive"))
    )
    (net (code "51") (name "Net-(J11-3)") (class "Default")
      (node (ref "J11") (pin "P3") (pinfunction "3_P3") (pintype "passive"))
      (node (ref "J9") (pin "P2") (pinfunction "2_P2") (pintype "passive"))
      (node (ref "R34") (pin "1") (pinfunction "1_1") (pintype "passive"))
    )
    (net (code "52") (name "Net-(J12-3)") (class "Default")
      (node (ref "J12") (pin "P3") (pinfunction "3_P3") (pintype "passive"))
      (node (ref "R35") (pin "1") (pinfunction "1_1") (pintype "passive"))
    )
    (net (code "53") (name "Net-(Q1-PadB)") (class "Default")
      (node (ref "Q1") (pin "B") (pinfunction "B_B") (pintype "passive"))
      (node (ref "Q2") (pin "B") (pinfunction "B_B") (pintype "passive"))
    )
    (net (code "54") (name "Net-(Q3-G)") (class "Default")
      (node (ref "D11") (pin "A") (pinfunction "A_A") (pintype "passive"))
      (node (ref "Q3") (pin "3") (pinfunction "G_3") (pintype "passive"))
      (node (ref "R32") (pin "1") (pinfunction "1_1") (pintype "passive"))
    )
    (net (code "55") (name "VCC") (class "Default")
      (node (ref "C2") (pin "1") (pinfunction "1_1") (pintype "passive"))
      (node (ref "C3") (pin "1") (pinfunction "1_1") (pintype "passive"))
      (node (ref "C6") (pin "1") (pinfunction "1_1") (pintype "passive"))
      (node (ref "C7") (pin "1") (pinfunction "1_1") (pintype "passive"))
      (node (ref "C9") (pin "1") (pinfunction "1_1") (pintype "passive"))
      (node (ref "IC1") (pin "4") (pinfunction "V+_4") (pintype "power_in"))
      (node (ref "IC2") (pin "5") (pinfunction "V+_5") (pintype "power_in"))
      (node (ref "IC3") (pin "4") (pinfunction "V+_4") (pintype "power_in"))
      (node (ref "IC4") (pin "4") (pinfunction "V+_4") (pintype "power_in"))
      (node (ref "IC5") (pin "5") (pinfunction "V+_5") (pintype "power_in"))
      (node (ref "L2") (pin "1") (pinfunction "1_1") (pintype "passive"))
      (node (ref "R15") (pin "2") (pinfunction "2_2") (pintype "passive"))
      (node (ref "R17") (pin "2") (pinfunction "2_2") (pintype "passive"))
      (node (ref "R24") (pin "2") (pinfunction "2_2") (pintype "passive"))
      (node (ref "R25") (pin "2") (pinfunction "2_2") (pintype "passive"))
      (node (ref "R33") (pin "1") (pinfunction "1_1") (pintype "passive"))
    )
    (net (code "56") (name "VEE") (class "Default")
      (node (ref "C1") (pin "2") (pinfunction "2_2") (pintype "passive"))
      (node (ref "C4") (pin "2") (pinfunction "2_2") (pintype "passive"))
      (node (ref "C5") (pin "2") (pinfunction "2_2") (pintype "passive"))
      (node (ref "C8") (pin "2") (pinfunction "2_2") (pintype "passive"))
      (node (ref "IC1") (pin "11") (pinfunction "V-_11") (pintype "power_in"))
      (node (ref "IC2") (pin "2") (pinfunction "V-_2") (pintype "power_in"))
      (node (ref "IC3") (pin "11") (pinfunction "V-_11") (pintype "power_in"))
      (node (ref "IC4") (pin "11") (pinfunction "V-_11") (pintype "power_in"))
      (node (ref "IC5") (pin "2") (pinfunction "V-_2") (pintype "power_in"))
      (node (ref "L1") (pin "1") (pinfunction "1_1") (pintype "passive"))
      (node (ref "R16") (pin "2") (pinfunction "2_2") (pintype "passive"))
      (node (ref "R18") (pin "2") (pinfunction "2_2") (pintype "passive"))
    )
    (net (code "57") (name "unconnected-(J2-2-PadP2)") (class "Default")
      (node (ref "J2") (pin "P2") (pinfunction "2_P2") (pintype "passive"))
    )
    (net (code "58") (name "unconnected-(J3-2-PadP2)") (class "Default")
      (node (ref "J3") (pin "P2") (pinfunction "2_P2") (pintype "passive"))
    )
    (net (code "59") (name "unconnected-(J4-2-PadP2)") (class "Default")
      (node (ref "J4") (pin "P2") (pinfunction "2_P2") (pintype "passive"))
    )
    (net (code "60") (name "unconnected-(J7-2-PadP2)") (class "Default")
      (node (ref "J7") (pin "P2") (pinfunction "2_P2") (pintype "passive"))
    )
    (net (code "61") (name "unconnected-(J8-2-PadP2)") (class "Default")
      (node (ref "J8") (pin "P2") (pinfunction "2_P2") (pintype "passive"))
    )
    (net (code "62") (name "unconnected-(J11-2-PadP2)") (class "Default")
      (node (ref "J11") (pin "P2") (pinfunction "2_P2") (pintype "passive"))
    )
    (net (code "63") (name "unconnected-(J12-2-PadP2)") (class "Default")
      (node (ref "J12") (pin "P2") (pinfunction "2_P2") (pintype "passive"))
    )
    (net (code "64") (name "unconnected-(Q2-PadC)") (class "Default")
      (node (ref "Q2") (pin "C") (pinfunction "C_C") (pintype "passive"))
    )
  )
)
